# Sheet_1_2025-06-24.net
KiCad netlist of a schematic drawn in Altium Designer
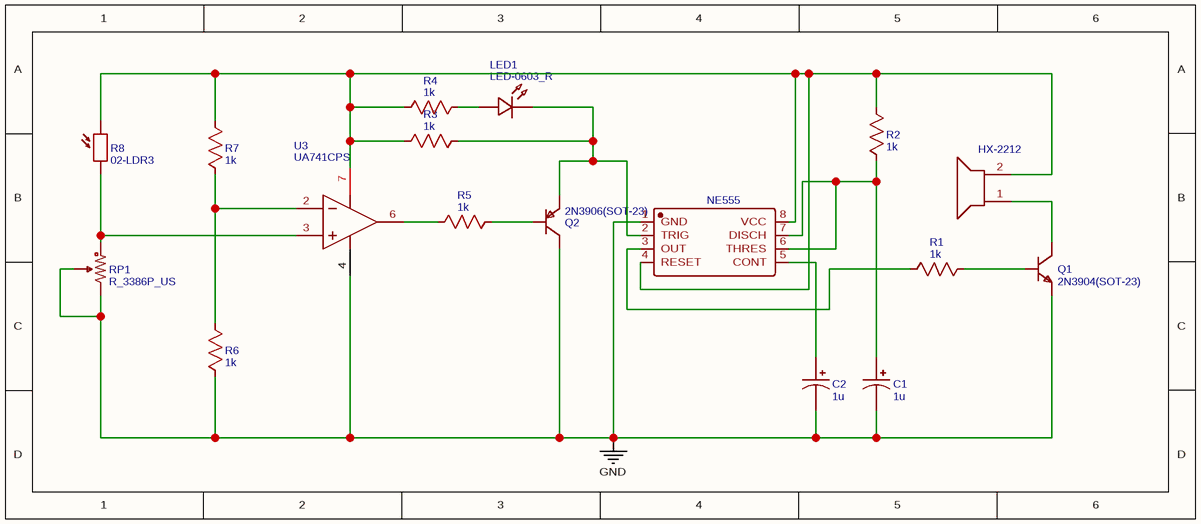
[diagram p0: Sheet_1_2025-06-24.schdoc]

(export (version "E")
  (design (tool "Eeschema 10.0.6"))
  (components
    (comp (ref "C1")
      (value "1u")
      (fields (field (name "CONTRIBUTOR") "LCEDA_Lib"))
      (libsource (lib "altium-import") (part "root_3_1u_"))
    )
    (comp (ref "C2")
      (value "1u")
      (fields (field (name "CONTRIBUTOR") "LCEDA_Lib"))
      (libsource (lib "altium-import") (part "root_3_1u_"))
    )
    (comp (ref "LED1")
      (value "LED-0603_R")
      (fields
        (field (name "MANUFACTURER") "EVERLIGHT(台湾亿光)")
        (field (name "MANUFACTURER PART") "19-217/R6C-AL1M2VY/3T")
        (field (name "CONTRIBUTOR") "LCEDA_01")
      )
      (libsource (lib "altium-import") (part "root_0_LED-0603_R_"))
    )
    (comp (ref "Q1")
      (value "2N3904(SOT-23)")
      (fields
        (field (name "MANUFACTURER") "KEC")
        (field (name "MANUFACTURER PART") "2n3904S-RTK/PS")
        (field (name "CONTRIBUTOR") "LCEDA_Lib")
      )
      (libsource (lib "altium-import") (part "root_0_2N3904(SOT-23)_"))
    )
    (comp (ref "Q2")
      (value "2N3906(SOT-23)")
      (fields
        (field (name "MANUFACTURER") "KEC")
        (field (name "MANUFACTURER PART") "2N3906S-RTK/PS")
        (field (name "CONTRIBUTOR") "LCEDA_Lib")
      )
      (libsource (lib "altium-import") (part "root_0_2N3906(SOT-23)_"))
    )
    (comp (ref "R1")
      (value "1k")
      (fields (field (name "CONTRIBUTOR") "LCEDA_Lib"))
      (libsource (lib "altium-import") (part "root_0_1k_"))
    )
    (comp (ref "R2")
      (value "1k")
      (fields (field (name "CONTRIBUTOR") "LCEDA_Lib"))
      (libsource (lib "altium-import") (part "root_1_1k_"))
    )
    (comp (ref "R3")
      (value "1k")
      (fields (field (name "CONTRIBUTOR") "LCEDA_Lib"))
      (libsource (lib "altium-import") (part "root_0_1k_"))
    )
    (comp (ref "R4")
      (value "1k")
      (fields (field (name "CONTRIBUTOR") "LCEDA_Lib"))
      (libsource (lib "altium-import") (part "root_0_1k_"))
    )
    (comp (ref "R5")
      (value "1k")
      (fields (field (name "CONTRIBUTOR") "LCEDA_Lib"))
      (libsource (lib "altium-import") (part "root_0_1k_"))
    )
    (comp (ref "R6")
      (value "1k")
      (fields (field (name "CONTRIBUTOR") "LCEDA_Lib"))
      (libsource (lib "altium-import") (part "root_1_1k_"))
    )
    (comp (ref "R7")
      (value "1k")
      (fields (field (name "CONTRIBUTOR") "LCEDA_Lib"))
      (libsource (lib "altium-import") (part "root_1_1k_"))
    )
    (comp (ref "R8")
      (value "02-LDR3")
      (fields (field (name "MANUFACTURER") "NTE Electronics") (field (name "CONTRIBUTOR") "lcsc"))
      (libsource (lib "altium-import") (part "root_1_02-LDR3_"))
    )
    (comp (ref "RP1")
      (value "R_3386P_US")
      (fields (field (name "CONTRIBUTOR") "LCEDA_Lib"))
      (libsource (lib "altium-import") (part "root_1_R_3386P_US_"))
    )
    (comp (ref "U1")
      (value "HX-2212")
      (fields (field (name "CONTRIBUTOR") "lcsc"))
      (libsource (lib "altium-import") (part "root_2_HX-2212_"))
    )
    (comp (ref "U2")
      (value "NE555")
      (fields (field (name "CONTRIBUTOR") "LCSC"))
      (libsource (lib "altium-import") (part "root_0_NE555_"))
    )
    (comp (ref "U3")
      (value "UA741CPS")
      (fields (field (name "MANUFACTURER") "TI(德州仪器)") (field (name "SUBPART_NO") "1"))
      (libsource (lib "altium-import") (part "root_0_UA741CPS_"))
    )
  )
  (nets
    (net (code "1") (name "GND") (class "Default")
      (node (ref "C1") (pin "2") (pinfunction "2_2") (pintype "passive"))
      (node (ref "C2") (pin "2") (pinfunction "2_2") (pintype "passive"))
      (node (ref "Q1") (pin "1") (pinfunction "E_1") (pintype "passive"))
      (node (ref "Q2") (pin "3") (pinfunction "C_3") (pintype "passive"))
      (node (ref "R6") (pin "1") (pinfunction "1_1") (pintype "passive"))
      (node (ref "RP1") (pin "2") (pinfunction "2_2") (pintype "passive"))
      (node (ref "RP1") (pin "3") (pinfunction "3_3") (pintype "passive"))
      (node (ref "U2") (pin "1") (pinfunction "GND_1") (pintype "passive"))
      (node (ref "U3") (pin "4") (pinfunction "VSS_4") (pintype "passive"))
    )
    (net (code "2") (name "Net-(LED1-Pad1)") (class "Default")
      (node (ref "LED1") (pin "1") (pinfunction "1_1") (pintype "passive"))
      (node (ref "R4") (pin "2") (pinfunction "2_2") (pintype "passive"))
    )
    (net (code "3") (name "Net-(Q1-B)") (class "Default")
      (node (ref "Q1") (pin "2") (pinfunction "B_2") (pintype "passive"))
      (node (ref "R1") (pin "2") (pinfunction "2_2") (pintype "passive"))
    )
    (net (code "4") (name "Net-(Q1-C)") (class "Default")
      (node (ref "Q1") (pin "3") (pinfunction "C_3") (pintype "passive"))
      (node (ref "U1") (pin "1") (pinfunction "1_1") (pintype "passive"))
    )
    (net (code "5") (name "Net-(Q2-B)") (class "Default")
      (node (ref "Q2") (pin "2") (pinfunction "B_2") (pintype "passive"))
      (node (ref "R5") (pin "2") (pinfunction "2_2") (pintype "passive"))
    )
    (net (code "6") (name "Net-(Q2-E)") (class "Default")
      (node (ref "LED1") (pin "2") (pinfunction "2_2") (pintype "passive"))
      (node (ref "Q2") (pin "1") (pinfunction "E_1") (pintype "passive"))
      (node (ref "R3") (pin "2") (pinfunction "2_2") (pintype "passive"))
      (node (ref "U2") (pin "2") (pinfunction "TRIG_2") (pintype "passive"))
    )
    (net (code "7") (name "Net-(U2-CONT)") (class "Default")
      (node (ref "C2") (pin "1") (pinfunction "1_1") (pintype "passive"))
      (node (ref "U2") (pin "5") (pinfunction "CONT_5") (pintype "passive"))
    )
    (net (code "8") (name "Net-(U2-DISCH)") (class "Default")
      (node (ref "C1") (pin "1") (pinfunction "1_1") (pintype "passive"))
      (node (ref "R2") (pin "1") (pinfunction "1_1") (pintype "passive"))
      (node (ref "U2") (pin "6") (pinfunction "THRES_6") (pintype "passive"))
      (node (ref "U2") (pin "7") (pinfunction "DISCH_7") (pintype "passive"))
    )
    (net (code "9") (name "Net-(U2-OUT)") (class "Default")
      (node (ref "R1") (pin "1") (pinfunction "1_1") (pintype "passive"))
      (node (ref "U2") (pin "3") (pinfunction "OUT_3") (pintype "passive"))
    )
    (net (code "10") (name "Net-(U2-RESET)") (class "Default")
      (node (ref "R2") (pin "2") (pinfunction "2_2") (pintype "passive"))
      (node (ref "R3") (pin "1") (pinfunction "1_1") (pintype "passive"))
      (node (ref "R4") (pin "1") (pinfunction "1_1") (pintype "passive"))
      (node (ref "R7") (pin "2") (pinfunction "2_2") (pintype "passive"))
      (node (ref "R8") (pin "2") (pinfunction "2_2") (pintype "passive"))
      (node (ref "U1") (pin "2") (pinfunction "2_2") (pintype "passive"))
      (node (ref "U2") (pin "4") (pinfunction "RESET_4") (pintype "passive"))
      (node (ref "U2") (pin "8") (pinfunction "VCC_8") (pintype "passive"))
      (node (ref "U3") (pin "7") (pinfunction "VDD_7") (pintype "passive"))
    )
    (net (code "11") (name "Net-(U3-+IN)") (class "Default")
      (node (ref "R8") (pin "1") (pinfunction "1_1") (pintype "passive"))
      (node (ref "RP1") (pin "1") (pinfunction "1_1") (pintype "passive"))
      (node (ref "U3") (pin "3") (pinfunction "+IN_3") (pintype "passive"))
    )
    (net (code "12") (name "Net-(U3--IN)") (class "Default")
      (node (ref "R6") (pin "2") (pinfunction "2_2") (pintype "passive"))
      (node (ref "R7") (pin "1") (pinfunction "1_1") (pintype "passive"))
      (node (ref "U3") (pin "2") (pinfunction "-IN_2") (pintype "passive"))
    )
    (net (code "13") (name "Net-(U3-OUT)") (class "Default")
      (node (ref "R5") (pin "1") (pinfunction "1_1") (pintype "passive"))
      (node (ref "U3") (pin "6") (pinfunction "OUT_6") (pintype "passive"))
    )
  )
)
